# CajitaAbierta_v05_robotique.net
KiCad netlist of a schematic drawn in EAGLE
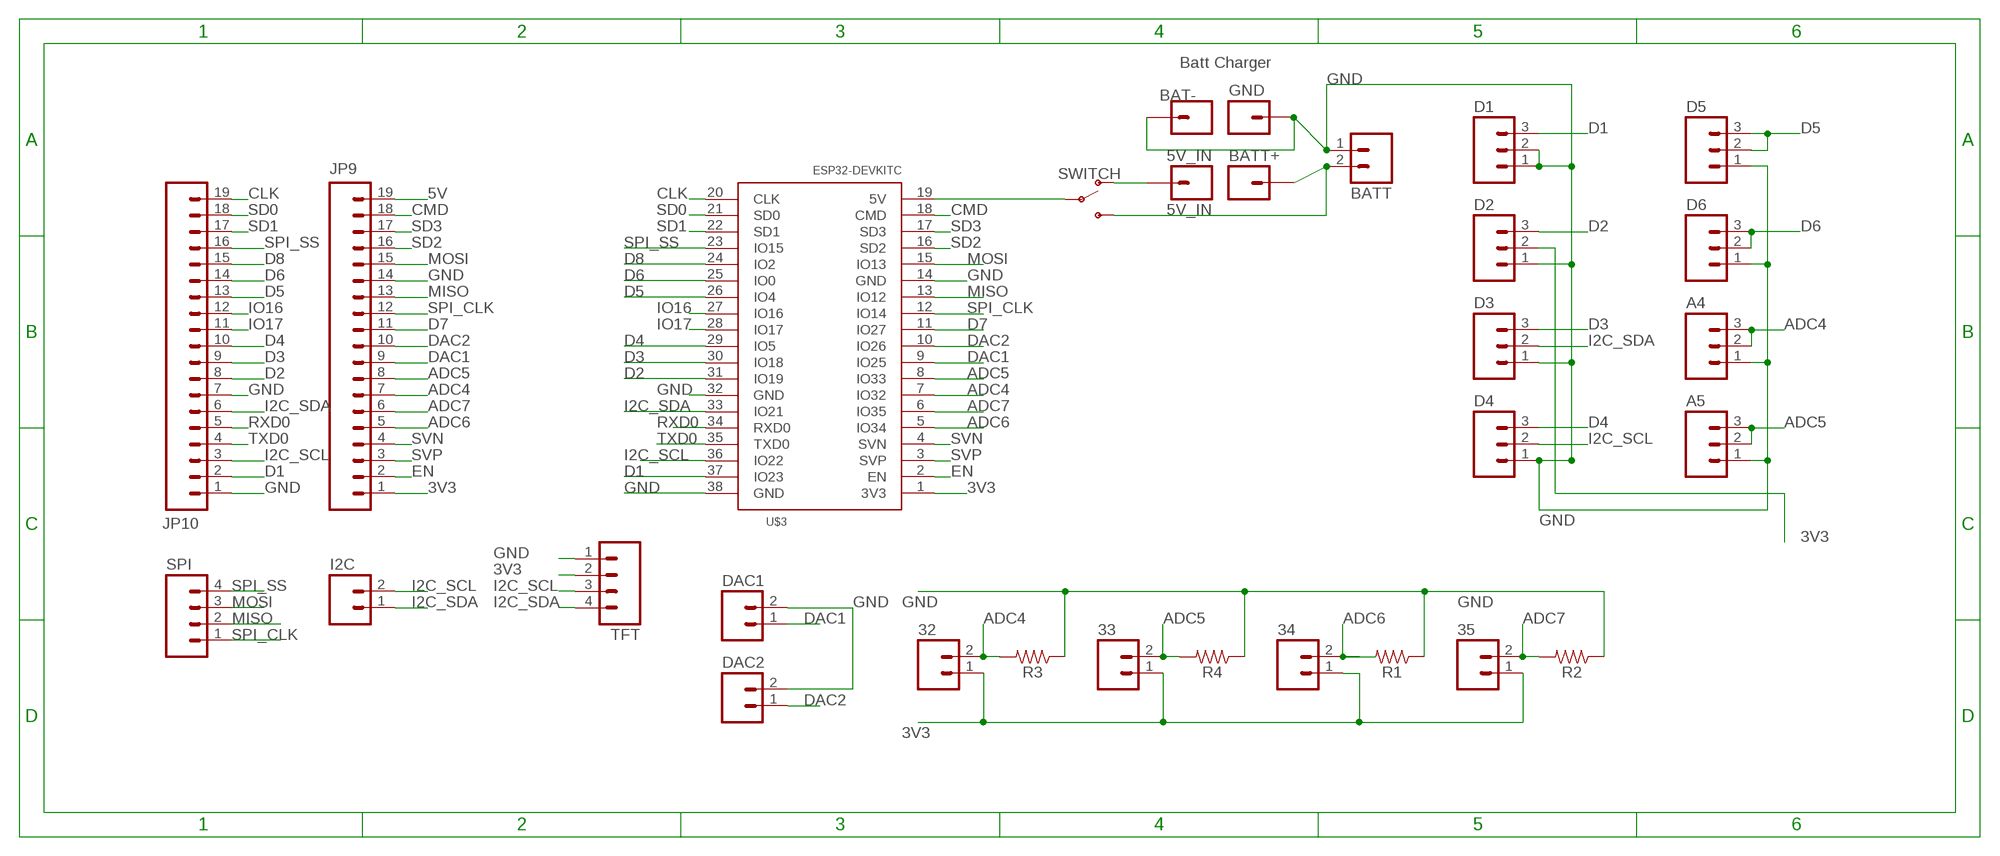
[diagram p0: schematic, sheet 1]

(export (version "E")
  (design (tool "Eeschema 10.0.6"))
  (components
    (comp (ref "5V_IN")
      (value "5V_IN")
      (footprint "eagle-import:1X01")
      (libsource (lib "eagle-import") (part "M01PTH"))
    )
    (comp (ref "32")
      (value "M02PTH")
      (footprint "eagle-import:1X02")
      (libsource (lib "eagle-import") (part "SparkFun-Connectors_6242394_M02PTH"))
    )
    (comp (ref "33")
      (value "M02PTH")
      (footprint "eagle-import:1X02")
      (libsource (lib "eagle-import") (part "SparkFun-Connectors_6242394_M02PTH"))
    )
    (comp (ref "34")
      (value "M02PTH")
      (footprint "eagle-import:1X02")
      (libsource (lib "eagle-import") (part "SparkFun-Connectors_6242394_M02PTH"))
    )
    (comp (ref "35")
      (value "M02PTH")
      (footprint "eagle-import:1X02")
      (libsource (lib "eagle-import") (part "SparkFun-Connectors_6242394_M02PTH"))
    )
    (comp (ref "A4")
      (value "M03LOCK_LONGPADS")
      (footprint "eagle-import:1X03_LOCK_LONGPADS")
      (libsource (lib "eagle-import") (part "M03LOCK_LONGPADS"))
    )
    (comp (ref "A5")
      (value "M03LOCK_LONGPADS")
      (footprint "eagle-import:1X03_LOCK_LONGPADS")
      (libsource (lib "eagle-import") (part "M03LOCK_LONGPADS"))
    )
    (comp (ref "BAT-")
      (value "M01PTH")
      (footprint "eagle-import:1X01")
      (libsource (lib "eagle-import") (part "M01PTH"))
    )
    (comp (ref "BATT")
      (value "M02LOCK_LONGPADS")
      (footprint "eagle-import:1X02_LOCK_LONGPADS")
      (libsource (lib "eagle-import") (part "M02LOCK_LONGPADS"))
    )
    (comp (ref "BATT+")
      (value "M01PTH")
      (footprint "eagle-import:1X01")
      (libsource (lib "eagle-import") (part "M01PTH"))
    )
    (comp (ref "D1")
      (value "M03LOCK_LONGPADS")
      (footprint "eagle-import:1X03_LOCK_LONGPADS")
      (libsource (lib "eagle-import") (part "M03LOCK_LONGPADS"))
    )
    (comp (ref "D2")
      (value "M03LOCK_LONGPADS")
      (footprint "eagle-import:1X03_LOCK_LONGPADS")
      (libsource (lib "eagle-import") (part "M03LOCK_LONGPADS"))
    )
    (comp (ref "D3")
      (value "M03LOCK_LONGPADS")
      (footprint "eagle-import:1X03_LOCK_LONGPADS")
      (libsource (lib "eagle-import") (part "M03LOCK_LONGPADS"))
    )
    (comp (ref "D4")
      (value "M03LOCK_LONGPADS")
      (footprint "eagle-import:1X03_LOCK_LONGPADS")
      (libsource (lib "eagle-import") (part "M03LOCK_LONGPADS"))
    )
    (comp (ref "D5")
      (value "M03LOCK_LONGPADS")
      (footprint "eagle-import:1X03_LOCK_LONGPADS")
      (libsource (lib "eagle-import") (part "M03LOCK_LONGPADS"))
    )
    (comp (ref "D6")
      (value "M03LOCK_LONGPADS")
      (footprint "eagle-import:1X03_LOCK_LONGPADS")
      (libsource (lib "eagle-import") (part "M03LOCK_LONGPADS"))
    )
    (comp (ref "DAC1")
      (value "M02PTH")
      (footprint "eagle-import:1X02")
      (libsource (lib "eagle-import") (part "SparkFun-Connectors_6242394_M02PTH"))
    )
    (comp (ref "DAC2")
      (value "M02PTH")
      (footprint "eagle-import:1X02")
      (libsource (lib "eagle-import") (part "SparkFun-Connectors_6242394_M02PTH"))
    )
    (comp (ref "GND")
      (value "Batt Charger")
      (footprint "eagle-import:1X01")
      (libsource (lib "eagle-import") (part "M01PTH"))
    )
    (comp (ref "I2C")
      (value "M02PTH")
      (footprint "eagle-import:1X02")
      (libsource (lib "eagle-import") (part "SparkFun-Connectors_6242394_M02PTH"))
    )
    (comp (ref "JP9")
      (value "M191X19")
      (footprint "eagle-import:1X19")
      (libsource (lib "eagle-import") (part "M191X19"))
    )
    (comp (ref "JP10")
      (value "M191X19")
      (footprint "eagle-import:1X19")
      (libsource (lib "eagle-import") (part "M191X19"))
    )
    (comp (ref "R1")
      (value "RESISTOR1206")
      (footprint "eagle-import:1206")
      (libsource (lib "eagle-import") (part "RESISTOR1206"))
    )
    (comp (ref "R2")
      (value "RESISTOR1206")
      (footprint "eagle-import:1206")
      (libsource (lib "eagle-import") (part "RESISTOR1206"))
    )
    (comp (ref "R3")
      (value "RESISTOR1206")
      (footprint "eagle-import:1206")
      (libsource (lib "eagle-import") (part "RESISTOR1206"))
    )
    (comp (ref "R4")
      (value "RESISTOR1206")
      (footprint "eagle-import:1206")
      (libsource (lib "eagle-import") (part "RESISTOR1206"))
    )
    (comp (ref "SPI")
      (value "M04PTH")
      (footprint "eagle-import:1X04")
      (libsource (lib "eagle-import") (part "M04PTH"))
    )
    (comp (ref "SWITCH")
      (value "SWITCH-SPDT-SMD-RIGHT-ANGLE")
      (footprint "eagle-import:SWITCH_SPST_SMD_A")
      (libsource (lib "eagle-import") (part "SWITCH-SPDT-SMD-RIGHT-ANGLE"))
    )
    (comp (ref "TFT")
      (value "M04PTH")
      (footprint "eagle-import:1X04")
      (libsource (lib "eagle-import") (part "M04PTH"))
    )
    (comp (ref "U$3")
      (value "ESP32DEVKITC")
      (footprint "eagle-import:ESP32-DEVKITC")
      (libsource (lib "eagle-import") (part "ESP32DEVKITC"))
    )
  )
  (nets
    (net (code "1") (name "/3V3") (class "Default")
      (node (ref "32") (pin "1") (pinfunction "1_1") (pintype "passive"))
      (node (ref "33") (pin "1") (pinfunction "1_1") (pintype "passive"))
      (node (ref "34") (pin "1") (pinfunction "1_1") (pintype "passive"))
      (node (ref "35") (pin "1") (pinfunction "1_1") (pintype "passive"))
      (node (ref "D2") (pin "2") (pinfunction "2_2") (pintype "passive"))
      (node (ref "JP9") (pin "1") (pinfunction "1_1") (pintype "passive"))
      (node (ref "TFT") (pin "2") (pinfunction "2_2") (pintype "passive"))
      (node (ref "U$3") (pin "1") (pinfunction "3V3_1") (pintype "bidirectional"))
    )
    (net (code "2") (name "/5V") (class "Default")
      (node (ref "JP9") (pin "19") (pinfunction "19_19") (pintype "passive"))
      (node (ref "SWITCH") (pin "2") (pinfunction "P_2") (pintype "passive"))
      (node (ref "U$3") (pin "19") (pinfunction "5V_19") (pintype "bidirectional"))
    )
    (net (code "3") (name "/ADC4") (class "Default")
      (node (ref "32") (pin "2") (pinfunction "2_2") (pintype "passive"))
      (node (ref "A4") (pin "2") (pinfunction "2_2") (pintype "passive"))
      (node (ref "A4") (pin "3") (pinfunction "3_3") (pintype "passive"))
      (node (ref "JP9") (pin "7") (pinfunction "7_7") (pintype "passive"))
      (node (ref "R3") (pin "2") (pinfunction "2_2") (pintype "passive"))
      (node (ref "U$3") (pin "7") (pinfunction "IO32_7") (pintype "bidirectional"))
    )
    (net (code "4") (name "/ADC5") (class "Default")
      (node (ref "33") (pin "2") (pinfunction "2_2") (pintype "passive"))
      (node (ref "A5") (pin "2") (pinfunction "2_2") (pintype "passive"))
      (node (ref "A5") (pin "3") (pinfunction "3_3") (pintype "passive"))
      (node (ref "JP9") (pin "8") (pinfunction "8_8") (pintype "passive"))
      (node (ref "R4") (pin "2") (pinfunction "2_2") (pintype "passive"))
      (node (ref "U$3") (pin "8") (pinfunction "IO33_8") (pintype "bidirectional"))
    )
    (net (code "5") (name "/ADC6") (class "Default")
      (node (ref "34") (pin "2") (pinfunction "2_2") (pintype "passive"))
      (node (ref "JP9") (pin "5") (pinfunction "5_5") (pintype "passive"))
      (node (ref "R1") (pin "2") (pinfunction "2_2") (pintype "passive"))
      (node (ref "U$3") (pin "5") (pinfunction "IO34_5") (pintype "bidirectional"))
    )
    (net (code "6") (name "/ADC7") (class "Default")
      (node (ref "35") (pin "2") (pinfunction "2_2") (pintype "passive"))
      (node (ref "JP9") (pin "6") (pinfunction "6_6") (pintype "passive"))
      (node (ref "R2") (pin "2") (pinfunction "2_2") (pintype "passive"))
      (node (ref "U$3") (pin "6") (pinfunction "IO35_6") (pintype "bidirectional"))
    )
    (net (code "7") (name "/CLK") (class "Default")
      (node (ref "JP10") (pin "19") (pinfunction "19_19") (pintype "passive"))
      (node (ref "U$3") (pin "20") (pinfunction "CLK_20") (pintype "bidirectional"))
    )
    (net (code "8") (name "/CMD") (class "Default")
      (node (ref "JP9") (pin "18") (pinfunction "18_18") (pintype "passive"))
      (node (ref "U$3") (pin "18") (pinfunction "CMD_18") (pintype "bidirectional"))
    )
    (net (code "9") (name "/D1") (class "Default")
      (node (ref "D1") (pin "3") (pinfunction "3_3") (pintype "passive"))
      (node (ref "JP10") (pin "2") (pinfunction "2_2") (pintype "passive"))
      (node (ref "U$3") (pin "37") (pinfunction "IO23_37") (pintype "bidirectional"))
    )
    (net (code "10") (name "/D2") (class "Default")
      (node (ref "D2") (pin "3") (pinfunction "3_3") (pintype "passive"))
      (node (ref "JP10") (pin "8") (pinfunction "8_8") (pintype "passive"))
      (node (ref "U$3") (pin "31") (pinfunction "IO19_31") (pintype "bidirectional"))
    )
    (net (code "11") (name "/D3") (class "Default")
      (node (ref "D3") (pin "3") (pinfunction "3_3") (pintype "passive"))
      (node (ref "JP10") (pin "9") (pinfunction "9_9") (pintype "passive"))
      (node (ref "U$3") (pin "30") (pinfunction "IO18_30") (pintype "bidirectional"))
    )
    (net (code "12") (name "/D4") (class "Default")
      (node (ref "D4") (pin "3") (pinfunction "3_3") (pintype "passive"))
      (node (ref "JP10") (pin "10") (pinfunction "10_10") (pintype "passive"))
      (node (ref "U$3") (pin "29") (pinfunction "IO5_29") (pintype "bidirectional"))
    )
    (net (code "13") (name "/D5") (class "Default")
      (node (ref "D5") (pin "2") (pinfunction "2_2") (pintype "passive"))
      (node (ref "D5") (pin "3") (pinfunction "3_3") (pintype "passive"))
      (node (ref "JP10") (pin "13") (pinfunction "13_13") (pintype "passive"))
      (node (ref "U$3") (pin "26") (pinfunction "IO4_26") (pintype "bidirectional"))
    )
    (net (code "14") (name "/D6") (class "Default")
      (node (ref "D6") (pin "2") (pinfunction "2_2") (pintype "passive"))
      (node (ref "D6") (pin "3") (pinfunction "3_3") (pintype "passive"))
      (node (ref "JP10") (pin "14") (pinfunction "14_14") (pintype "passive"))
      (node (ref "U$3") (pin "25") (pinfunction "IO0_25") (pintype "bidirectional"))
    )
    (net (code "15") (name "/D7") (class "Default")
      (node (ref "JP9") (pin "11") (pinfunction "11_11") (pintype "passive"))
      (node (ref "U$3") (pin "11") (pinfunction "IO27_11") (pintype "bidirectional"))
    )
    (net (code "16") (name "/D8") (class "Default")
      (node (ref "JP10") (pin "15") (pinfunction "15_15") (pintype "passive"))
      (node (ref "U$3") (pin "24") (pinfunction "IO2_24") (pintype "bidirectional"))
    )
    (net (code "17") (name "/DAC1") (class "Default")
      (node (ref "DAC1") (pin "1") (pinfunction "1_1") (pintype "passive"))
      (node (ref "JP9") (pin "9") (pinfunction "9_9") (pintype "passive"))
      (node (ref "U$3") (pin "9") (pinfunction "IO25_9") (pintype "bidirectional"))
    )
    (net (code "18") (name "/DAC2") (class "Default")
      (node (ref "DAC2") (pin "1") (pinfunction "1_1") (pintype "passive"))
      (node (ref "JP9") (pin "10") (pinfunction "10_10") (pintype "passive"))
      (node (ref "U$3") (pin "10") (pinfunction "IO26_10") (pintype "bidirectional"))
    )
    (net (code "19") (name "/EN") (class "Default")
      (node (ref "JP9") (pin "2") (pinfunction "2_2") (pintype "passive"))
      (node (ref "U$3") (pin "2") (pinfunction "EN_2") (pintype "bidirectional"))
    )
    (net (code "20") (name "/GND") (class "Default")
      (node (ref "A4") (pin "1") (pinfunction "1_1") (pintype "passive"))
      (node (ref "A5") (pin "1") (pinfunction "1_1") (pintype "passive"))
      (node (ref "BAT-") (pin "1") (pinfunction "1_1") (pintype "passive"))
      (node (ref "BATT") (pin "1") (pinfunction "1_1") (pintype "passive"))
      (node (ref "D1") (pin "1") (pinfunction "1_1") (pintype "passive"))
      (node (ref "D1") (pin "2") (pinfunction "2_2") (pintype "passive"))
      (node (ref "D2") (pin "1") (pinfunction "1_1") (pintype "passive"))
      (node (ref "D3") (pin "1") (pinfunction "1_1") (pintype "passive"))
      (node (ref "D4") (pin "1") (pinfunction "1_1") (pintype "passive"))
      (node (ref "D5") (pin "1") (pinfunction "1_1") (pintype "passive"))
      (node (ref "D6") (pin "1") (pinfunction "1_1") (pintype "passive"))
      (node (ref "DAC1") (pin "2") (pinfunction "2_2") (pintype "passive"))
      (node (ref "DAC2") (pin "2") (pinfunction "2_2") (pintype "passive"))
      (node (ref "GND") (pin "1") (pinfunction "1_1") (pintype "passive"))
      (node (ref "JP10") (pin "1") (pinfunction "1_1") (pintype "passive"))
      (node (ref "JP10") (pin "7") (pinfunction "7_7") (pintype "passive"))
      (node (ref "JP9") (pin "14") (pinfunction "14_14") (pintype "passive"))
      (node (ref "R1") (pin "1") (pinfunction "1_1") (pintype "passive"))
      (node (ref "R2") (pin "1") (pinfunction "1_1") (pintype "passive"))
      (node (ref "R3") (pin "1") (pinfunction "1_1") (pintype "passive"))
      (node (ref "R4") (pin "1") (pinfunction "1_1") (pintype "passive"))
      (node (ref "TFT") (pin "1") (pinfunction "1_1") (pintype "passive"))
      (node (ref "U$3") (pin "14") (pinfunction "GND_14") (pintype "bidirectional"))
      (node (ref "U$3") (pin "32") (pinfunction "GND_32") (pintype "bidirectional"))
      (node (ref "U$3") (pin "38") (pinfunction "GND_38") (pintype "bidirectional"))
    )
    (net (code "21") (name "/I2C_SCL") (class "Default")
      (node (ref "D4") (pin "2") (pinfunction "2_2") (pintype "passive"))
      (node (ref "I2C") (pin "2") (pinfunction "2_2") (pintype "passive"))
      (node (ref "JP10") (pin "3") (pinfunction "3_3") (pintype "passive"))
      (node (ref "TFT") (pin "3") (pinfunction "3_3") (pintype "passive"))
      (node (ref "U$3") (pin "36") (pinfunction "IO22_36") (pintype "bidirectional"))
    )
    (net (code "22") (name "/I2C_SDA") (class "Default")
      (node (ref "D3") (pin "2") (pinfunction "2_2") (pintype "passive"))
      (node (ref "I2C") (pin "1") (pinfunction "1_1") (pintype "passive"))
      (node (ref "JP10") (pin "6") (pinfunction "6_6") (pintype "passive"))
      (node (ref "TFT") (pin "4") (pinfunction "4_4") (pintype "passive"))
      (node (ref "U$3") (pin "33") (pinfunction "IO21_33") (pintype "bidirectional"))
    )
    (net (code "23") (name "/IO16") (class "Default")
      (node (ref "JP10") (pin "12") (pinfunction "12_12") (pintype "passive"))
      (node (ref "U$3") (pin "27") (pinfunction "IO16_27") (pintype "bidirectional"))
    )
    (net (code "24") (name "/IO17") (class "Default")
      (node (ref "JP10") (pin "11") (pinfunction "11_11") (pintype "passive"))
      (node (ref "U$3") (pin "28") (pinfunction "IO17_28") (pintype "bidirectional"))
    )
    (net (code "25") (name "/MISO") (class "Default")
      (node (ref "JP9") (pin "13") (pinfunction "13_13") (pintype "passive"))
      (node (ref "SPI") (pin "2") (pinfunction "2_2") (pintype "passive"))
      (node (ref "U$3") (pin "13") (pinfunction "IO12_13") (pintype "bidirectional"))
    )
    (net (code "26") (name "/MOSI") (class "Default")
      (node (ref "JP9") (pin "15") (pinfunction "15_15") (pintype "passive"))
      (node (ref "SPI") (pin "3") (pinfunction "3_3") (pintype "passive"))
      (node (ref "U$3") (pin "15") (pinfunction "IO13_15") (pintype "bidirectional"))
    )
    (net (code "27") (name "/RXD0") (class "Default")
      (node (ref "JP10") (pin "5") (pinfunction "5_5") (pintype "passive"))
      (node (ref "U$3") (pin "34") (pinfunction "RXD0_34") (pintype "bidirectional"))
    )
    (net (code "28") (name "/SD0") (class "Default")
      (node (ref "JP10") (pin "18") (pinfunction "18_18") (pintype "passive"))
      (node (ref "U$3") (pin "21") (pinfunction "SD0_21") (pintype "bidirectional"))
    )
    (net (code "29") (name "/SD1") (class "Default")
      (node (ref "JP10") (pin "17") (pinfunction "17_17") (pintype "passive"))
      (node (ref "U$3") (pin "22") (pinfunction "SD1_22") (pintype "bidirectional"))
    )
    (net (code "30") (name "/SD2") (class "Default")
      (node (ref "JP9") (pin "16") (pinfunction "16_16") (pintype "passive"))
      (node (ref "U$3") (pin "16") (pinfunction "SD2_16") (pintype "bidirectional"))
    )
    (net (code "31") (name "/SD3") (class "Default")
      (node (ref "JP9") (pin "17") (pinfunction "17_17") (pintype "passive"))
      (node (ref "U$3") (pin "17") (pinfunction "SD3_17") (pintype "bidirectional"))
    )
    (net (code "32") (name "/SPI_CLK") (class "Default")
      (node (ref "JP9") (pin "12") (pinfunction "12_12") (pintype "passive"))
      (node (ref "SPI") (pin "1") (pinfunction "1_1") (pintype "passive"))
      (node (ref "U$3") (pin "12") (pinfunction "IO14_12") (pintype "bidirectional"))
    )
    (net (code "33") (name "/SPI_SS") (class "Default")
      (node (ref "JP10") (pin "16") (pinfunction "16_16") (pintype "passive"))
      (node (ref "SPI") (pin "4") (pinfunction "4_4") (pintype "passive"))
      (node (ref "U$3") (pin "23") (pinfunction "IO15_23") (pintype "bidirectional"))
    )
    (net (code "34") (name "/SVN") (class "Default")
      (node (ref "JP9") (pin "4") (pinfunction "4_4") (pintype "passive"))
      (node (ref "U$3") (pin "4") (pinfunction "SVN_4") (pintype "bidirectional"))
    )
    (net (code "35") (name "/SVP") (class "Default")
      (node (ref "JP9") (pin "3") (pinfunction "3_3") (pintype "passive"))
      (node (ref "U$3") (pin "3") (pinfunction "SVP_3") (pintype "bidirectional"))
    )
    (net (code "36") (name "/TXD0") (class "Default")
      (node (ref "JP10") (pin "4") (pinfunction "4_4") (pintype "passive"))
      (node (ref "U$3") (pin "35") (pinfunction "TXD0_35") (pintype "bidirectional"))
    )
    (net (code "37") (name "Net-(SWITCH-O)") (class "Default")
      (node (ref "5V_IN") (pin "1") (pinfunction "1_1") (pintype "passive"))
      (node (ref "SWITCH") (pin "1") (pinfunction "O_1") (pintype "passive"))
    )
    (net (code "38") (name "Net-(SWITCH-S)") (class "Default")
      (node (ref "BATT") (pin "2") (pinfunction "2_2") (pintype "passive"))
      (node (ref "BATT+") (pin "1") (pinfunction "1_1") (pintype "passive"))
      (node (ref "SWITCH") (pin "3") (pinfunction "S_3") (pintype "passive"))
    )
  )
)
